# 454_stereo_mic_Rev020000.net
KiCad netlist of a schematic drawn in EAGLE
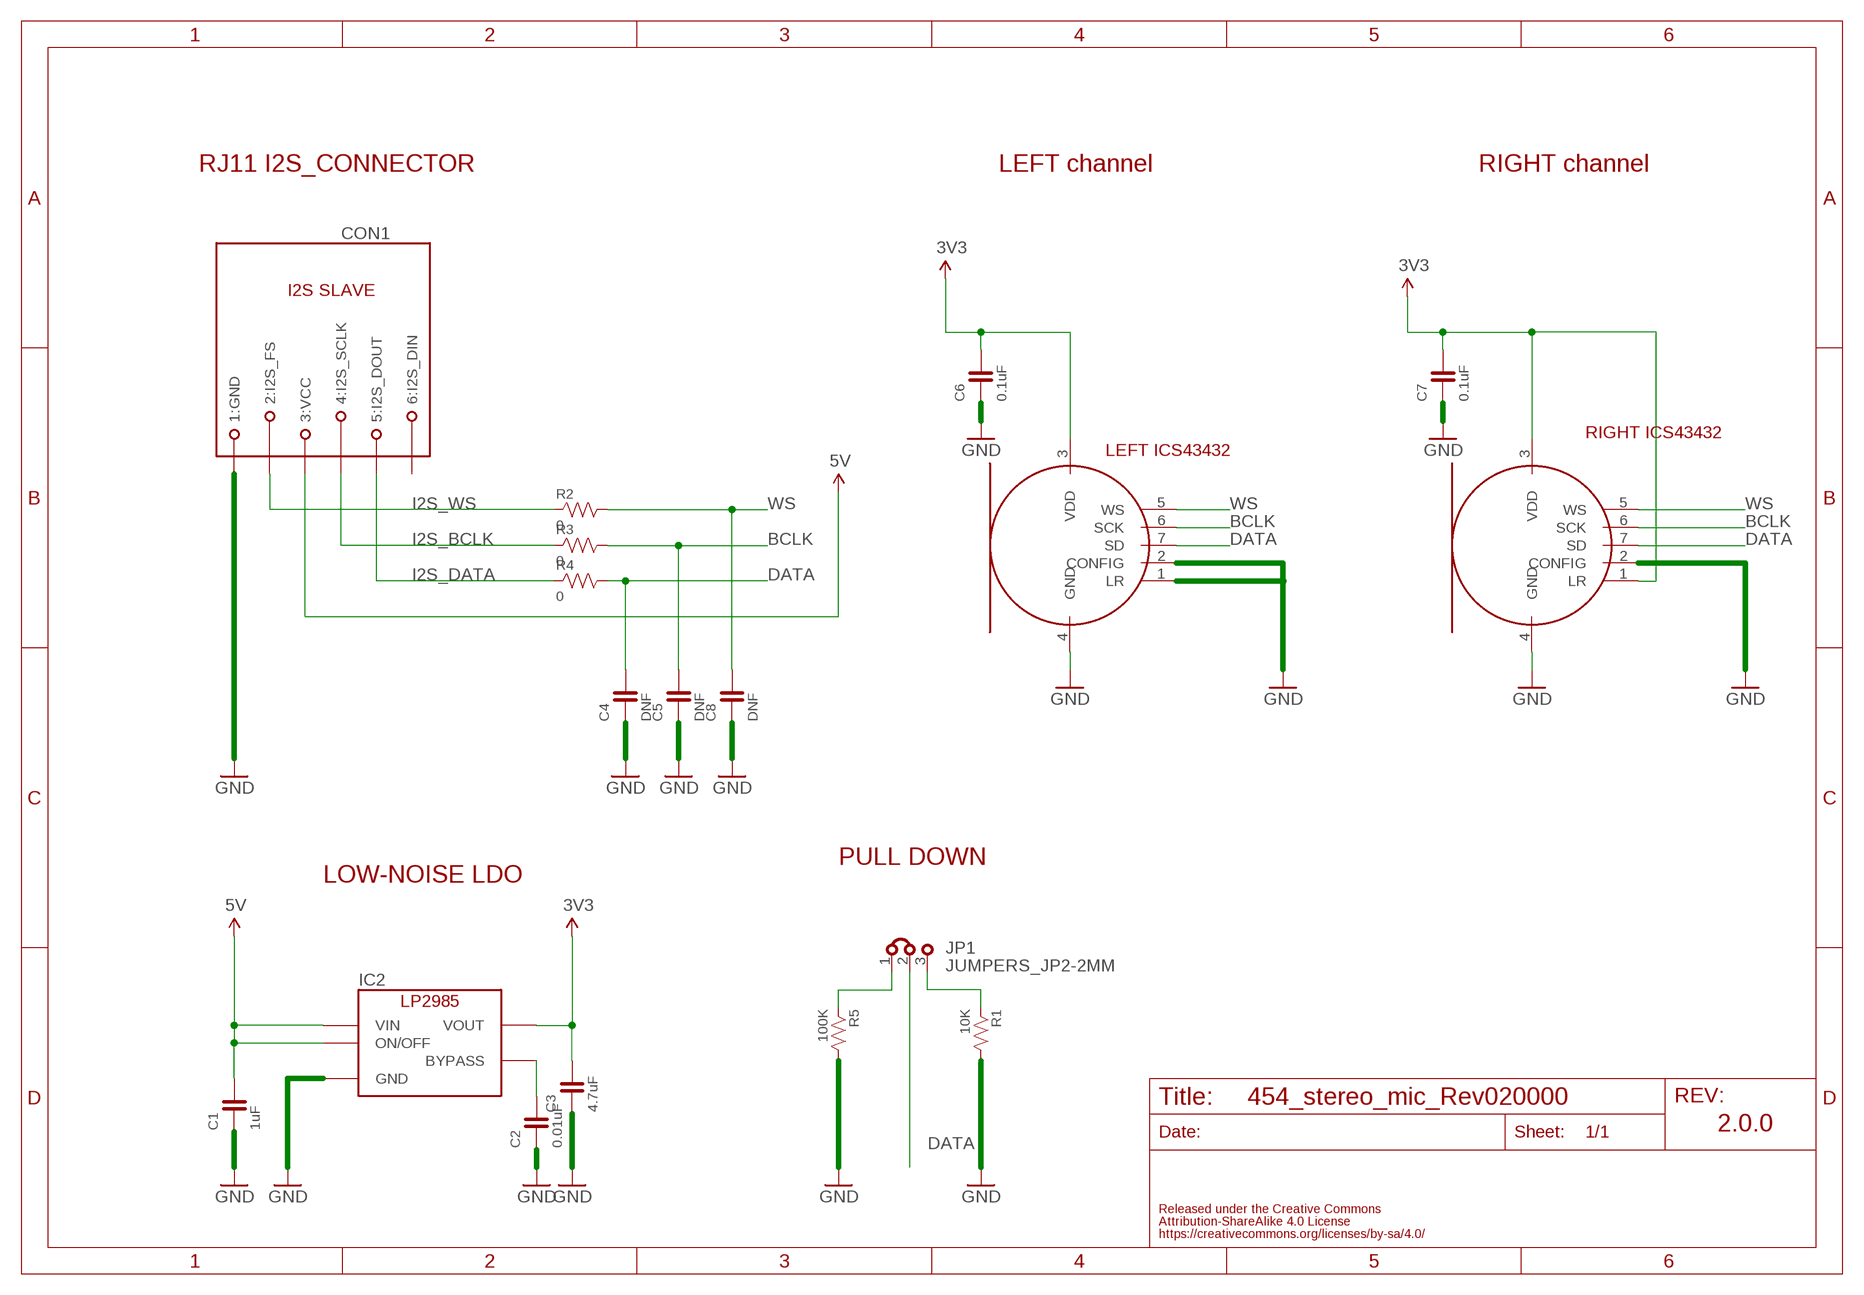
[diagram p0: schematic, sheet 1]

(export (version "E")
  (design (tool "Eeschema 10.0.6"))
  (components
    (comp (ref "C1")
      (value "1uF")
      (footprint "eagle-import:0603")
      (libsource (lib "eagle-import") (part "CAPACITOR-0603"))
    )
    (comp (ref "C2")
      (value "0.01uF")
      (footprint "eagle-import:0603")
      (libsource (lib "eagle-import") (part "CAPACITOR-0603"))
    )
    (comp (ref "C3")
      (value "4.7uF")
      (footprint "eagle-import:0603")
      (libsource (lib "eagle-import") (part "CAPACITOR-0603"))
    )
    (comp (ref "C4")
      (value "DNF")
      (footprint "eagle-import:0603")
      (libsource (lib "eagle-import") (part "CAPACITOR-0603"))
    )
    (comp (ref "C5")
      (value "DNF")
      (footprint "eagle-import:0603")
      (libsource (lib "eagle-import") (part "CAPACITOR-0603"))
    )
    (comp (ref "C6")
      (value "0.1uF")
      (footprint "eagle-import:0603")
      (libsource (lib "eagle-import") (part "CAPACITOR-0603"))
    )
    (comp (ref "C7")
      (value "0.1uF")
      (footprint "eagle-import:0603")
      (libsource (lib "eagle-import") (part "CAPACITOR-0603"))
    )
    (comp (ref "C8")
      (value "DNF")
      (footprint "eagle-import:0603")
      (libsource (lib "eagle-import") (part "CAPACITOR-0603"))
    )
    (comp (ref "CON1")
      (value "MODULAR-JACK-6P-RJ11_I2S_SLAVE")
      (footprint "eagle-import:7002-6PXC-X")
      (libsource (lib "eagle-import") (part "MODULAR-JACK-6P-RJ11_I2S_SLAVE"))
    )
    (comp (ref "IC2")
      (value "LP2985-33DBV")
      (footprint "eagle-import:SOT-23-5")
      (libsource (lib "eagle-import") (part "LP2985-33DBV"))
    )
    (comp (ref "JP1")
      (value "JUMPERS_JP2-2MM")
      (footprint "eagle-import:JUMPERS_JP2-2MM")
      (libsource (lib "eagle-import") (part "JUMPERS_JP2-2MM"))
    )
    (comp (ref "MIC_LEFT")
      (value "TDK-ICS43432")
      (footprint "eagle-import:TDK-ICS43432")
      (libsource (lib "eagle-import") (part "TDK-ICS43432"))
    )
    (comp (ref "MIC_RIGHT")
      (value "TDK-ICS43432")
      (footprint "eagle-import:TDK-ICS43432")
      (libsource (lib "eagle-import") (part "TDK-ICS43432"))
    )
    (comp (ref "R1")
      (value "10K")
      (footprint "eagle-import:0603")
      (libsource (lib "eagle-import") (part "RESISTOR-0603"))
    )
    (comp (ref "R2")
      (value "0")
      (footprint "eagle-import:0603")
      (libsource (lib "eagle-import") (part "RESISTOR-0603"))
    )
    (comp (ref "R3")
      (value "0")
      (footprint "eagle-import:0603")
      (libsource (lib "eagle-import") (part "RESISTOR-0603"))
    )
    (comp (ref "R4")
      (value "0")
      (footprint "eagle-import:0603")
      (libsource (lib "eagle-import") (part "RESISTOR-0603"))
    )
    (comp (ref "R5")
      (value "100K")
      (footprint "eagle-import:0603")
      (libsource (lib "eagle-import") (part "RESISTOR-0603"))
    )
  )
  (nets
    (net (code "1") (name "/BCLK") (class "Default")
      (node (ref "C5") (pin "2") (pinfunction "2_2") (pintype "passive"))
      (node (ref "MIC_LEFT") (pin "6") (pinfunction "SCK_6") (pintype "bidirectional"))
      (node (ref "MIC_RIGHT") (pin "6") (pinfunction "SCK_6") (pintype "bidirectional"))
      (node (ref "R3") (pin "2") (pinfunction "2_2") (pintype "bidirectional"))
    )
    (net (code "2") (name "/DATA") (class "Default")
      (node (ref "C4") (pin "2") (pinfunction "2_2") (pintype "passive"))
      (node (ref "JP1") (pin "2") (pinfunction "2_2") (pintype "passive"))
      (node (ref "MIC_LEFT") (pin "7") (pinfunction "SD_7") (pintype "bidirectional"))
      (node (ref "MIC_RIGHT") (pin "7") (pinfunction "SD_7") (pintype "bidirectional"))
      (node (ref "R4") (pin "2") (pinfunction "2_2") (pintype "bidirectional"))
    )
    (net (code "3") (name "/I2S_BCLK") (class "Default")
      (node (ref "CON1") (pin "4") (pinfunction "4:I2S_SCLK_4") (pintype "bidirectional"))
      (node (ref "R3") (pin "1") (pinfunction "1_1") (pintype "bidirectional"))
    )
    (net (code "4") (name "/I2S_DATA") (class "Default")
      (node (ref "CON1") (pin "5") (pinfunction "5:I2S_DOUT_5") (pintype "output"))
      (node (ref "R4") (pin "1") (pinfunction "1_1") (pintype "bidirectional"))
    )
    (net (code "5") (name "/I2S_WS") (class "Default")
      (node (ref "CON1") (pin "2") (pinfunction "2:I2S_FS_2") (pintype "bidirectional"))
      (node (ref "R2") (pin "1") (pinfunction "1_1") (pintype "bidirectional"))
    )
    (net (code "6") (name "/WS") (class "Default")
      (node (ref "C8") (pin "2") (pinfunction "2_2") (pintype "passive"))
      (node (ref "MIC_LEFT") (pin "5") (pinfunction "WS_5") (pintype "bidirectional"))
      (node (ref "MIC_RIGHT") (pin "5") (pinfunction "WS_5") (pintype "bidirectional"))
      (node (ref "R2") (pin "2") (pinfunction "2_2") (pintype "bidirectional"))
    )
    (net (code "7") (name "3V3") (class "Default")
      (node (ref "C3") (pin "2") (pinfunction "2_2") (pintype "passive"))
      (node (ref "C6") (pin "2") (pinfunction "2_2") (pintype "passive"))
      (node (ref "C7") (pin "2") (pinfunction "2_2") (pintype "passive"))
      (node (ref "IC2") (pin "5") (pinfunction "VOUT_5") (pintype "output"))
      (node (ref "MIC_LEFT") (pin "3") (pinfunction "VDD_3") (pintype "bidirectional"))
      (node (ref "MIC_RIGHT") (pin "1") (pinfunction "LR_1") (pintype "bidirectional"))
      (node (ref "MIC_RIGHT") (pin "3") (pinfunction "VDD_3") (pintype "bidirectional"))
    )
    (net (code "8") (name "5V") (class "Default")
      (node (ref "C1") (pin "2") (pinfunction "2_2") (pintype "passive"))
      (node (ref "CON1") (pin "3") (pinfunction "3:VCC_3") (pintype "power_in"))
      (node (ref "IC2") (pin "1") (pinfunction "VIN_1") (pintype "input"))
      (node (ref "IC2") (pin "3") (pinfunction "ON/OFF_3") (pintype "input"))
    )
    (net (code "9") (name "GND") (class "Default")
      (node (ref "C1") (pin "1") (pinfunction "1_1") (pintype "passive"))
      (node (ref "C2") (pin "1") (pinfunction "1_1") (pintype "passive"))
      (node (ref "C3") (pin "1") (pinfunction "1_1") (pintype "passive"))
      (node (ref "C4") (pin "1") (pinfunction "1_1") (pintype "passive"))
      (node (ref "C5") (pin "1") (pinfunction "1_1") (pintype "passive"))
      (node (ref "C6") (pin "1") (pinfunction "1_1") (pintype "passive"))
      (node (ref "C7") (pin "1") (pinfunction "1_1") (pintype "passive"))
      (node (ref "C8") (pin "1") (pinfunction "1_1") (pintype "passive"))
      (node (ref "CON1") (pin "1") (pinfunction "1:GND_1") (pintype "power_in"))
      (node (ref "IC2") (pin "2") (pinfunction "GND_2") (pintype "power_in"))
      (node (ref "MIC_LEFT") (pin "1") (pinfunction "LR_1") (pintype "bidirectional"))
      (node (ref "MIC_LEFT") (pin "2") (pinfunction "CONFIG_2") (pintype "bidirectional"))
      (node (ref "MIC_LEFT") (pin "4") (pinfunction "GND_4") (pintype "bidirectional"))
      (node (ref "MIC_RIGHT") (pin "2") (pinfunction "CONFIG_2") (pintype "bidirectional"))
      (node (ref "MIC_RIGHT") (pin "4") (pinfunction "GND_4") (pintype "bidirectional"))
      (node (ref "R1") (pin "2") (pinfunction "2_2") (pintype "bidirectional"))
      (node (ref "R5") (pin "2") (pinfunction "2_2") (pintype "bidirectional"))
    )
    (net (code "10") (name "Net-(IC2-BYPASS)") (class "Default")
      (node (ref "C2") (pin "2") (pinfunction "2_2") (pintype "passive"))
      (node (ref "IC2") (pin "4") (pinfunction "BYPASS_4") (pintype "bidirectional"))
    )
    (net (code "11") (name "Net-(JP1-Pad1)") (class "Default")
      (node (ref "JP1") (pin "1") (pinfunction "1_1") (pintype "passive"))
      (node (ref "R5") (pin "1") (pinfunction "1_1") (pintype "bidirectional"))
    )
    (net (code "12") (name "Net-(JP1-Pad3)") (class "Default")
      (node (ref "JP1") (pin "3") (pinfunction "3_3") (pintype "passive"))
      (node (ref "R1") (pin "1") (pinfunction "1_1") (pintype "bidirectional"))
    )
    (net (code "13") (name "unconnected-(CON1-6:I2S_DIN-Pad6)") (class "Default")
      (node (ref "CON1") (pin "6") (pinfunction "6:I2S_DIN_6") (pintype "input"))
    )
  )
)
